# wheel-opto-sensor-v2.net
KiCad netlist of a schematic drawn in EAGLE
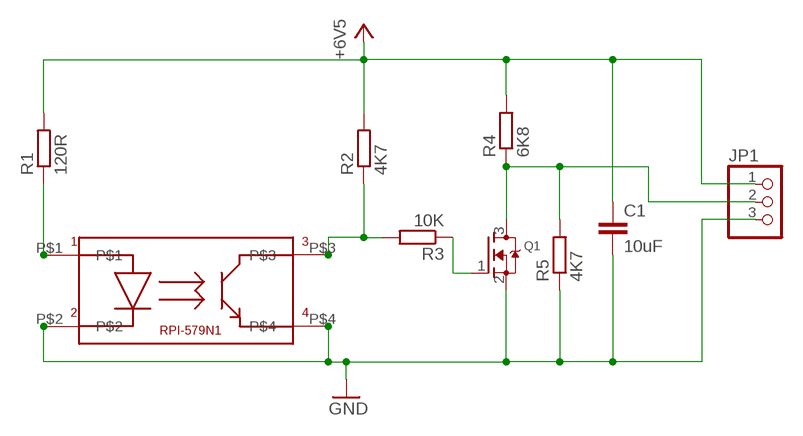
[diagram p0: schematic, sheet 1]

(export (version "E")
  (design (tool "Eeschema 10.0.6"))
  (components
    (comp (ref "C1")
      (value "10uF")
      (footprint "eagle-import:C1206")
      (libsource (lib "eagle-import") (part "C-EUC1206"))
    )
    (comp (ref "JP1")
      (value "PINHD-1X3")
      (footprint "eagle-import:1X03")
      (libsource (lib "eagle-import") (part "PINHD-1X3"))
    )
    (comp (ref "Q1")
      (value "MOSFET-NREFLOW")
      (footprint "eagle-import:SOT23")
      (libsource (lib "eagle-import") (part "MOSFET-NREFLOW"))
    )
    (comp (ref "R1")
      (value "120R")
      (footprint "eagle-import:M0805")
      (libsource (lib "eagle-import") (part "R-EU_M0805"))
    )
    (comp (ref "R2")
      (value "4K7")
      (footprint "eagle-import:M0805")
      (libsource (lib "eagle-import") (part "R-EU_M0805"))
    )
    (comp (ref "R3")
      (value "10K")
      (footprint "eagle-import:M0805")
      (libsource (lib "eagle-import") (part "R-EU_M0805"))
    )
    (comp (ref "R4")
      (value "6K8")
      (footprint "eagle-import:M0805")
      (libsource (lib "eagle-import") (part "R-EU_M0805"))
    )
    (comp (ref "R5")
      (value "4K7")
      (footprint "eagle-import:M0805")
      (libsource (lib "eagle-import") (part "R-EU_M0805"))
    )
    (comp (ref "U$1")
      (value "RPI-579N1")
      (footprint "eagle-import:RPI-579N1")
      (libsource (lib "eagle-import") (part "RPI-579N1"))
    )
  )
  (nets
    (net (code "1") (name "+6V5") (class "Default")
      (node (ref "C1") (pin "1") (pinfunction "1_1") (pintype "passive"))
      (node (ref "JP1") (pin "1") (pinfunction "1_1") (pintype "passive"))
      (node (ref "R1") (pin "2") (pinfunction "2_2") (pintype "passive"))
      (node (ref "R2") (pin "2") (pinfunction "2_2") (pintype "passive"))
      (node (ref "R4") (pin "2") (pinfunction "2_2") (pintype "passive"))
    )
    (net (code "2") (name "GND") (class "Default")
      (node (ref "C1") (pin "2") (pinfunction "2_2") (pintype "passive"))
      (node (ref "JP1") (pin "3") (pinfunction "3_3") (pintype "passive"))
      (node (ref "Q1") (pin "2") (pinfunction "S_2") (pintype "bidirectional"))
      (node (ref "R5") (pin "1") (pinfunction "1_1") (pintype "passive"))
      (node (ref "U$1") (pin "P$2") (pinfunction "P$2_P$2") (pintype "bidirectional"))
      (node (ref "U$1") (pin "P$4") (pinfunction "P$4_P$4") (pintype "bidirectional"))
    )
    (net (code "3") (name "Net-(Q1-D)") (class "Default")
      (node (ref "JP1") (pin "2") (pinfunction "2_2") (pintype "passive"))
      (node (ref "Q1") (pin "3") (pinfunction "D_3") (pintype "bidirectional"))
      (node (ref "R4") (pin "1") (pinfunction "1_1") (pintype "passive"))
      (node (ref "R5") (pin "2") (pinfunction "2_2") (pintype "passive"))
    )
    (net (code "4") (name "Net-(Q1-G)") (class "Default")
      (node (ref "Q1") (pin "1") (pinfunction "G_1") (pintype "bidirectional"))
      (node (ref "R3") (pin "1") (pinfunction "1_1") (pintype "passive"))
    )
    (net (code "5") (name "Net-(R1-Pad1)") (class "Default")
      (node (ref "R1") (pin "1") (pinfunction "1_1") (pintype "passive"))
      (node (ref "U$1") (pin "P$1") (pinfunction "P$1_P$1") (pintype "bidirectional"))
    )
    (net (code "6") (name "Net-(R2-Pad1)") (class "Default")
      (node (ref "R2") (pin "1") (pinfunction "1_1") (pintype "passive"))
      (node (ref "R3") (pin "2") (pinfunction "2_2") (pintype "passive"))
      (node (ref "U$1") (pin "P$3") (pinfunction "P$3_P$3") (pintype "bidirectional"))
    )
  )
)
